# IoT_Pro_04.net
KiCad netlist of a schematic drawn in EAGLE
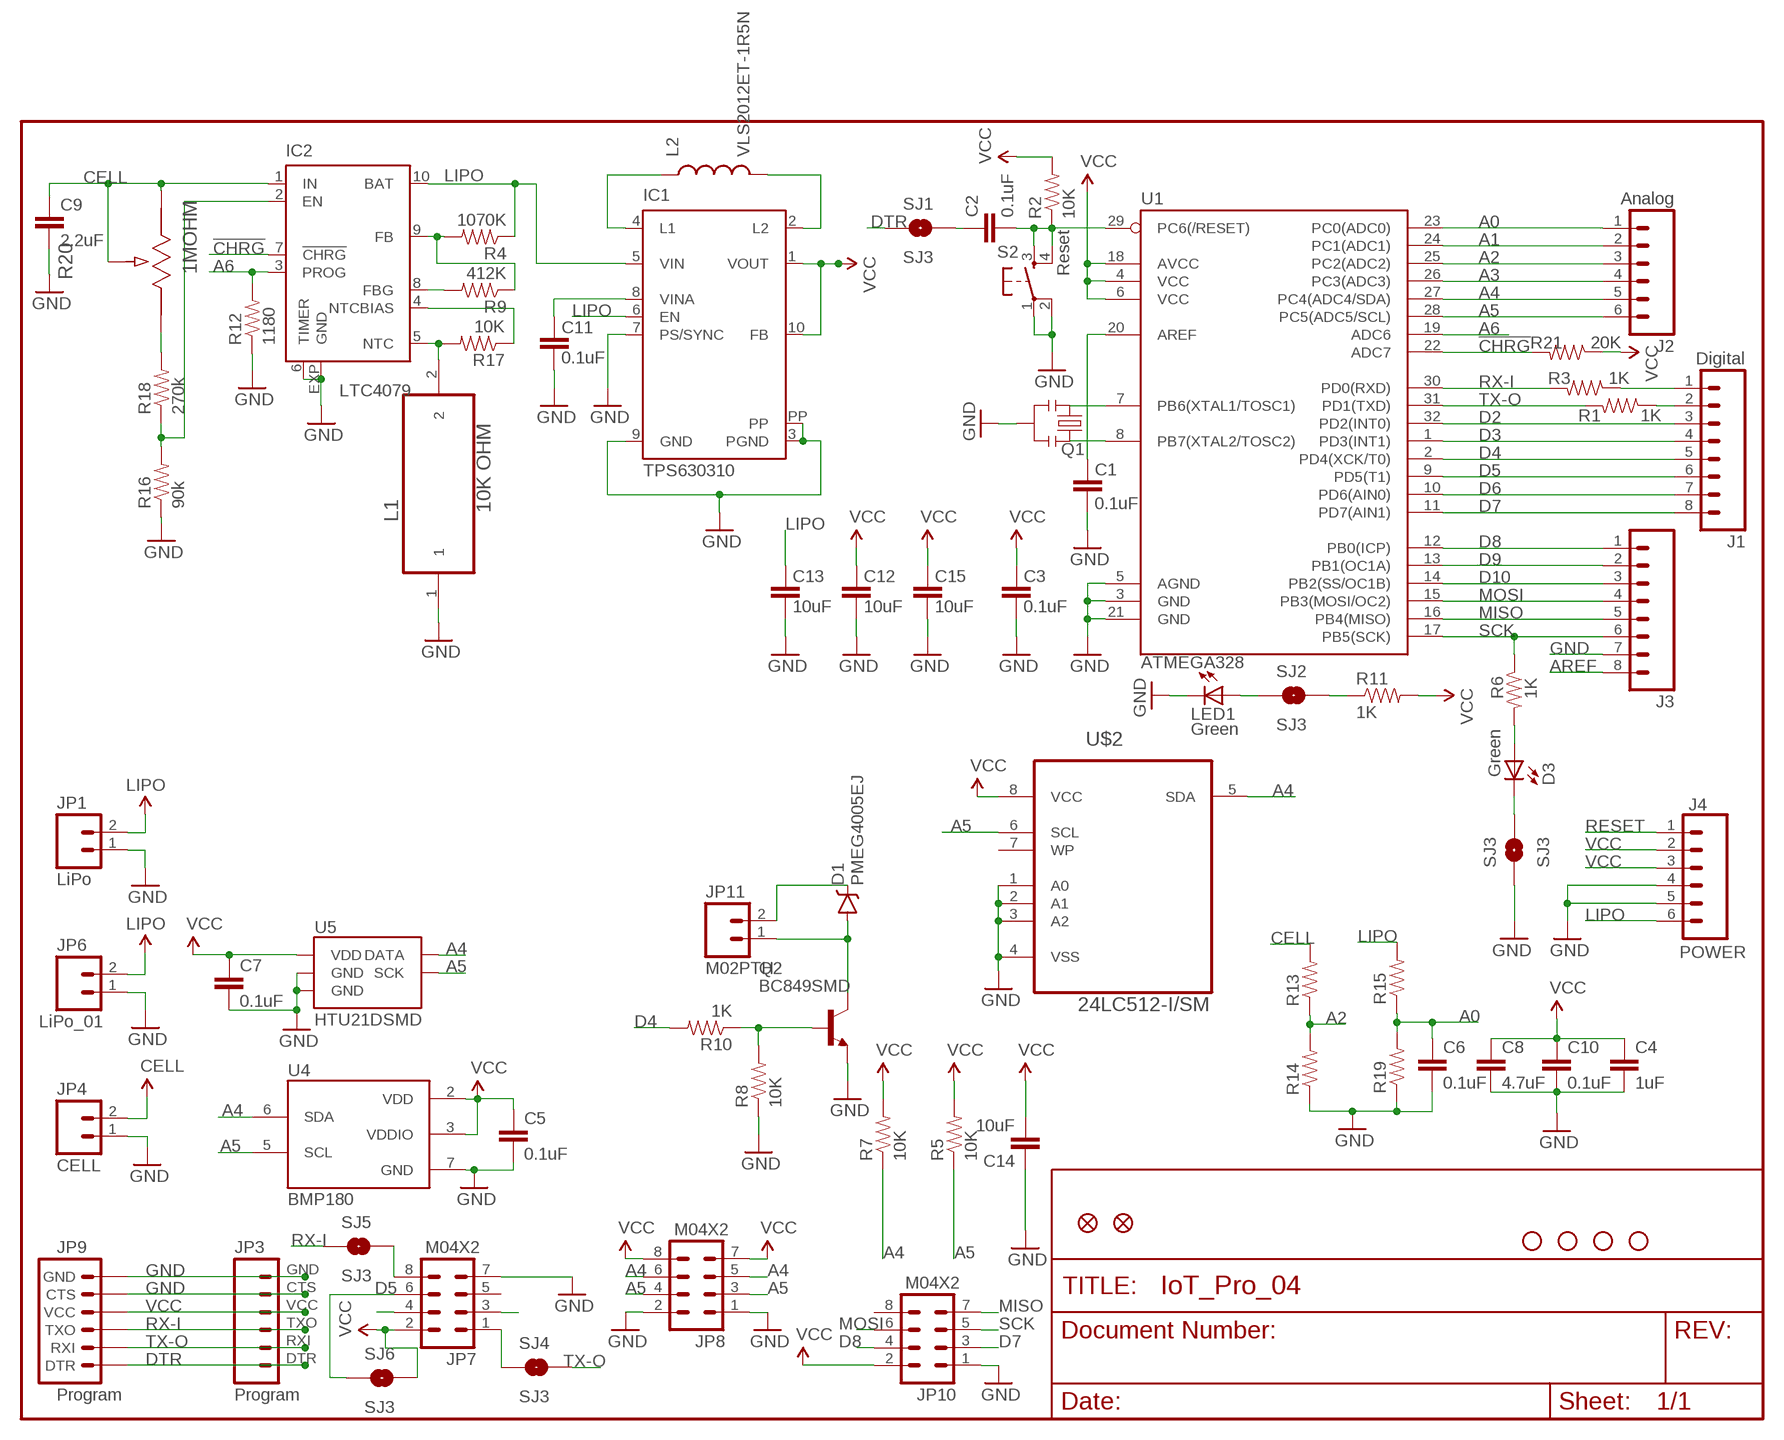
[diagram p0: schematic, sheet 1]

(export (version "E")
  (design (tool "Eeschema 10.0.6"))
  (components
    (comp (ref "C1")
      (value "0.1uF")
      (footprint "eagle-import:0805")
      (libsource (lib "eagle-import") (part "CAP0805"))
    )
    (comp (ref "C2")
      (value "0.1uF")
      (footprint "eagle-import:0805")
      (libsource (lib "eagle-import") (part "CAP0805"))
    )
    (comp (ref "C3")
      (value "0.1uF")
      (footprint "eagle-import:0805")
      (libsource (lib "eagle-import") (part "CAP0805"))
    )
    (comp (ref "C4")
      (value "1uF")
      (footprint "eagle-import:0805")
      (libsource (lib "eagle-import") (part "CAP0805"))
    )
    (comp (ref "C5")
      (value "0.1uF")
      (footprint "eagle-import:0805")
      (libsource (lib "eagle-import") (part "CAP0805"))
    )
    (comp (ref "C6")
      (value "0.1uF")
      (footprint "eagle-import:0805")
      (libsource (lib "eagle-import") (part "CAP0805"))
    )
    (comp (ref "C7")
      (value "0.1uF")
      (footprint "eagle-import:0805")
      (libsource (lib "eagle-import") (part "CAP0805"))
    )
    (comp (ref "C8")
      (value "4.7uF")
      (footprint "eagle-import:0805")
      (libsource (lib "eagle-import") (part "CAP0805"))
    )
    (comp (ref "C9")
      (value "2.2uF")
      (footprint "eagle-import:0805")
      (libsource (lib "eagle-import") (part "CAP0805"))
    )
    (comp (ref "C10")
      (value "0.1uF")
      (footprint "eagle-import:0805")
      (libsource (lib "eagle-import") (part "CAP0805"))
    )
    (comp (ref "C11")
      (value "0.1uF")
      (footprint "eagle-import:0805")
      (libsource (lib "eagle-import") (part "CAP0805"))
    )
    (comp (ref "C12")
      (value "10uF")
      (footprint "eagle-import:0805")
      (libsource (lib "eagle-import") (part "CAP0805"))
    )
    (comp (ref "C13")
      (value "10uF")
      (footprint "eagle-import:0805")
      (libsource (lib "eagle-import") (part "CAP0805"))
    )
    (comp (ref "C14")
      (value "10uF")
      (footprint "eagle-import:0805")
      (libsource (lib "eagle-import") (part "SparkFun-Passives_CAP0805"))
    )
    (comp (ref "C15")
      (value "10uF")
      (footprint "eagle-import:0805")
      (libsource (lib "eagle-import") (part "CAP0805"))
    )
    (comp (ref "D1")
      (value "PMEG4005EJ")
      (footprint "eagle-import:SOD-323")
      (libsource (lib "eagle-import") (part "DIODE-SCHOTTKY-PMEG4005EJ"))
    )
    (comp (ref "D3")
      (value "Green")
      (footprint "eagle-import:PLCC2")
      (libsource (lib "eagle-import") (part "_T679-?-1E1F1LG"))
    )
    (comp (ref "IC1")
      (value "TPS630310")
      (footprint "eagle-import:S-PDSO-N10")
      (fields (field (name "MPN") "TPS61200DRCT"))
      (libsource (lib "eagle-import") (part "TPS630310"))
    )
    (comp (ref "IC2")
      (value "LTC4079")
      (footprint "eagle-import:DFN10-3X3")
      (fields (field (name "MPN") "LTC4062EDD#PBF"))
      (libsource (lib "eagle-import") (part "LTC4079"))
    )
    (comp (ref "J1")
      (value "Digital")
      (footprint "eagle-import:1X08")
      (libsource (lib "eagle-import") (part "M081X08"))
    )
    (comp (ref "J2")
      (value "Analog")
      (footprint "eagle-import:1X06")
      (libsource (lib "eagle-import") (part "M06SIP"))
    )
    (comp (ref "J3")
      (value "M081X08")
      (footprint "eagle-import:1X08")
      (libsource (lib "eagle-import") (part "M081X08"))
    )
    (comp (ref "J4")
      (value "POWER")
      (footprint "eagle-import:1X06")
      (libsource (lib "eagle-import") (part "M06SIP"))
    )
    (comp (ref "JP1")
      (value "LiPo")
      (footprint "eagle-import:MOLEX-1X2")
      (libsource (lib "eagle-import") (part "SparkFun-Connectors_M02POLAR"))
    )
    (comp (ref "JP2")
      (value "FIDUCIAL1X2.5")
      (footprint "eagle-import:FIDUCIAL-1X2.5")
      (libsource (lib "eagle-import") (part "FIDUCIAL1X2.5"))
    )
    (comp (ref "JP3")
      (value "Program")
      (footprint "eagle-import:1X06")
      (libsource (lib "eagle-import") (part "SparkFun-Connectors_M06SIP"))
    )
    (comp (ref "JP4")
      (value "CELL")
      (footprint "eagle-import:MOLEX-1X2")
      (libsource (lib "eagle-import") (part "SparkFun-Connectors_M02POLAR"))
    )
    (comp (ref "JP5")
      (value "FIDUCIAL1X2.5")
      (footprint "eagle-import:FIDUCIAL-1X2.5")
      (libsource (lib "eagle-import") (part "FIDUCIAL1X2.5"))
    )
    (comp (ref "JP6")
      (value "LiPo_01")
      (footprint "eagle-import:1X02")
      (libsource (lib "eagle-import") (part "M02PTH"))
    )
    (comp (ref "JP7")
      (value "M04X2")
      (footprint "eagle-import:2X4")
      (libsource (lib "eagle-import") (part "M04X2"))
    )
    (comp (ref "JP8")
      (value "M04X2")
      (footprint "eagle-import:2X4")
      (libsource (lib "eagle-import") (part "M04X2"))
    )
    (comp (ref "JP9")
      (value "Program")
      (footprint "eagle-import:1X06-SMD")
      (libsource (lib "eagle-import") (part "ARDUINO_SERIAL_PROGRAMSMD"))
    )
    (comp (ref "JP10")
      (value "M04X2")
      (footprint "eagle-import:2X4")
      (libsource (lib "eagle-import") (part "M04X2"))
    )
    (comp (ref "JP11")
      (value "M02PTH")
      (footprint "eagle-import:1X02")
      (libsource (lib "eagle-import") (part "SparkFun-Connectors_M02PTH"))
    )
    (comp (ref "L1")
      (value "10K OHM")
      (footprint "eagle-import:THERM_B57421V2103J62")
      (fields (field (name "MPN") "B57421V2103J62") (field (name "TOLERANCE") "±5%"))
      (libsource (lib "eagle-import") (part "B57421V2103J62"))
    )
    (comp (ref "L2")
      (value "VLS2012ET-1R5N")
      (footprint "eagle-import:1007")
      (libsource (lib "eagle-import") (part "INDUCTOR1007"))
    )
    (comp (ref "LED1")
      (value "Green")
      (footprint "eagle-import:PLCC2")
      (libsource (lib "eagle-import") (part "_T679-?-1E1F1LG"))
    )
    (comp (ref "Q1")
      (value "8MHZ")
      (footprint "eagle-import:RESONATOR-SMD")
      (libsource (lib "eagle-import") (part "RESONATOR8MHZ"))
    )
    (comp (ref "Q2")
      (value "BC849SMD")
      (footprint "eagle-import:SOT23-BEC")
      (libsource (lib "eagle-import") (part "BC849SMD"))
    )
    (comp (ref "R1")
      (value "1K")
      (footprint "eagle-import:0805")
      (libsource (lib "eagle-import") (part "RESISTOR0805-RES"))
    )
    (comp (ref "R2")
      (value "10K")
      (footprint "eagle-import:0805")
      (libsource (lib "eagle-import") (part "RESISTOR0805-RES"))
    )
    (comp (ref "R3")
      (value "1K")
      (footprint "eagle-import:0805")
      (libsource (lib "eagle-import") (part "RESISTOR0805-RES"))
    )
    (comp (ref "R4")
      (value "1070K")
      (footprint "eagle-import:0805")
      (libsource (lib "eagle-import") (part "RESISTOR0805-RES"))
    )
    (comp (ref "R5")
      (value "10K")
      (footprint "eagle-import:0805")
      (libsource (lib "eagle-import") (part "RESISTOR0805-RES"))
    )
    (comp (ref "R6")
      (value "1K")
      (footprint "eagle-import:0805")
      (libsource (lib "eagle-import") (part "RESISTOR0805-RES"))
    )
    (comp (ref "R7")
      (value "10K")
      (footprint "eagle-import:0805")
      (libsource (lib "eagle-import") (part "RESISTOR0805-RES"))
    )
    (comp (ref "R8")
      (value "10K")
      (footprint "eagle-import:0805")
      (libsource (lib "eagle-import") (part "RESISTOR0805-RES"))
    )
    (comp (ref "R9")
      (value "412K")
      (footprint "eagle-import:0805")
      (libsource (lib "eagle-import") (part "RESISTOR0805-RES"))
    )
    (comp (ref "R10")
      (value "1K")
      (footprint "eagle-import:0805")
      (libsource (lib "eagle-import") (part "RESISTOR0805-RES"))
    )
    (comp (ref "R11")
      (value "1K")
      (footprint "eagle-import:0805")
      (libsource (lib "eagle-import") (part "RESISTOR0805-RES"))
    )
    (comp (ref "R12")
      (value "1180")
      (footprint "eagle-import:0805")
      (libsource (lib "eagle-import") (part "RESISTOR0805-RES"))
    )
    (comp (ref "R13")
      (value "RESISTOR0805-RES")
      (footprint "eagle-import:0805")
      (libsource (lib "eagle-import") (part "SparkFun-Passives_RESISTOR0805-RES"))
    )
    (comp (ref "R14")
      (value "RESISTOR0805-RES")
      (footprint "eagle-import:0805")
      (libsource (lib "eagle-import") (part "SparkFun-Passives_RESISTOR0805-RES"))
    )
    (comp (ref "R15")
      (value "RESISTOR0805-RES")
      (footprint "eagle-import:0805")
      (libsource (lib "eagle-import") (part "SparkFun-Passives_RESISTOR0805-RES"))
    )
    (comp (ref "R16")
      (value "90k")
      (footprint "eagle-import:0805")
      (libsource (lib "eagle-import") (part "RESISTOR0805-RES"))
    )
    (comp (ref "R17")
      (value "10K")
      (footprint "eagle-import:0805")
      (libsource (lib "eagle-import") (part "RESISTOR0805-RES"))
    )
    (comp (ref "R18")
      (value "270k")
      (footprint "eagle-import:0805")
      (libsource (lib "eagle-import") (part "RESISTOR0805-RES"))
    )
    (comp (ref "R19")
      (value "RESISTOR0805-RES")
      (footprint "eagle-import:0805")
      (libsource (lib "eagle-import") (part "SparkFun-Passives_RESISTOR0805-RES"))
    )
    (comp (ref "R20")
      (value "1MOHM")
      (footprint "eagle-import:POT_EVM2N")
      (fields (field (name "MPN") "EVM2NSX80B16") (field (name "TOLERANCE") "±25 %"))
      (libsource (lib "eagle-import") (part "EVM-2N2NSX80B16"))
    )
    (comp (ref "R21")
      (value "20K")
      (footprint "eagle-import:0805")
      (libsource (lib "eagle-import") (part "RESISTOR0805-RES"))
    )
    (comp (ref "S2")
      (value "Reset")
      (footprint "eagle-import:TACTILE_SWITCH_SMD")
      (libsource (lib "eagle-import") (part "TAC_SWITCHSMD"))
    )
    (comp (ref "SJ1")
      (value "SJ3")
      (footprint "eagle-import:SJ_2S-NOTRACE")
      (libsource (lib "eagle-import") (part "SOLDERJUMPERNC2"))
    )
    (comp (ref "SJ2")
      (value "SJ3")
      (footprint "eagle-import:SJ_2S-NOTRACE")
      (libsource (lib "eagle-import") (part "SOLDERJUMPERNC2"))
    )
    (comp (ref "SJ3")
      (value "SJ3")
      (footprint "eagle-import:SJ_2S-NOTRACE")
      (libsource (lib "eagle-import") (part "SOLDERJUMPERNC2"))
    )
    (comp (ref "SJ4")
      (value "SJ3")
      (footprint "eagle-import:SJ_2S-NOTRACE")
      (libsource (lib "eagle-import") (part "SOLDERJUMPERNC2"))
    )
    (comp (ref "SJ5")
      (value "SJ3")
      (footprint "eagle-import:SJ_2S-NOTRACE")
      (libsource (lib "eagle-import") (part "SOLDERJUMPERNC2"))
    )
    (comp (ref "SJ6")
      (value "SJ3")
      (footprint "eagle-import:SJ_2S-NOTRACE")
      (libsource (lib "eagle-import") (part "SOLDERJUMPERNC2"))
    )
    (comp (ref "U$1")
      (value "STAND-OFFTIGHT")
      (footprint "eagle-import:STAND-OFF-TIGHT")
      (libsource (lib "eagle-import") (part "STAND-OFFTIGHT"))
    )
    (comp (ref "U$2")
      (value "24LC512-I/SM")
      (footprint "eagle-import:SOIC127P794X203-8N")
      (libsource (lib "eagle-import") (part "24LC512-I/SM"))
    )
    (comp (ref "U$3")
      (value "STAND-OFFTIGHT")
      (footprint "eagle-import:STAND-OFF-TIGHT")
      (libsource (lib "eagle-import") (part "STAND-OFFTIGHT"))
    )
    (comp (ref "U$9")
      (value "STAND-OFFTIGHT")
      (footprint "eagle-import:STAND-OFF-TIGHT")
      (libsource (lib "eagle-import") (part "STAND-OFFTIGHT"))
    )
    (comp (ref "U$10")
      (value "STAND-OFFTIGHT")
      (footprint "eagle-import:STAND-OFF-TIGHT")
      (libsource (lib "eagle-import") (part "STAND-OFFTIGHT"))
    )
    (comp (ref "U1")
      (value "ATMEGA328")
      (footprint "eagle-import:TQFP32-08")
      (libsource (lib "eagle-import") (part "ATMEGA168"))
    )
    (comp (ref "U4")
      (value "BMP180")
      (footprint "eagle-import:BMP180")
      (libsource (lib "eagle-import") (part "BMP180"))
    )
    (comp (ref "U5")
      (value "HTU21DSMD")
      (footprint "eagle-import:HTU21D")
      (libsource (lib "eagle-import") (part "HTU21DSMD"))
    )
  )
  (nets
    (net (code "1") (name "/A0") (class "Default")
      (node (ref "C6") (pin "1") (pinfunction "1_1") (pintype "passive"))
      (node (ref "J2") (pin "1") (pinfunction "1_1") (pintype "passive"))
      (node (ref "R15") (pin "1") (pinfunction "1_1") (pintype "passive"))
      (node (ref "R19") (pin "2") (pinfunction "2_2") (pintype "passive"))
      (node (ref "U1") (pin "23") (pinfunction "PC0(ADC0)_23") (pintype "bidirectional"))
    )
    (net (code "2") (name "/A1") (class "Default")
      (node (ref "J2") (pin "2") (pinfunction "2_2") (pintype "passive"))
      (node (ref "U1") (pin "24") (pinfunction "PC1(ADC1)_24") (pintype "bidirectional"))
    )
    (net (code "3") (name "/A2") (class "Default")
      (node (ref "J2") (pin "3") (pinfunction "3_3") (pintype "passive"))
      (node (ref "R13") (pin "1") (pinfunction "1_1") (pintype "passive"))
      (node (ref "R14") (pin "2") (pinfunction "2_2") (pintype "passive"))
      (node (ref "U1") (pin "25") (pinfunction "PC2(ADC2)_25") (pintype "bidirectional"))
    )
    (net (code "4") (name "/A3") (class "Default")
      (node (ref "J2") (pin "4") (pinfunction "4_4") (pintype "passive"))
      (node (ref "U1") (pin "26") (pinfunction "PC3(ADC3)_26") (pintype "bidirectional"))
    )
    (net (code "5") (name "/A4") (class "Default")
      (node (ref "J2") (pin "5") (pinfunction "5_5") (pintype "passive"))
      (node (ref "JP8") (pin "5") (pinfunction "5_5") (pintype "passive"))
      (node (ref "JP8") (pin "6") (pinfunction "6_6") (pintype "passive"))
      (node (ref "R7") (pin "1") (pinfunction "1_1") (pintype "passive"))
      (node (ref "U$2") (pin "5") (pinfunction "SDA_5") (pintype "bidirectional"))
      (node (ref "U1") (pin "27") (pinfunction "PC4(ADC4/SDA)_27") (pintype "bidirectional"))
      (node (ref "U4") (pin "6") (pinfunction "SDA_6") (pintype "bidirectional"))
      (node (ref "U5") (pin "DATA") (pinfunction "DATA_DATA") (pintype "bidirectional"))
    )
    (net (code "6") (name "/A5") (class "Default")
      (node (ref "J2") (pin "6") (pinfunction "6_6") (pintype "passive"))
      (node (ref "JP8") (pin "3") (pinfunction "3_3") (pintype "passive"))
      (node (ref "JP8") (pin "4") (pinfunction "4_4") (pintype "passive"))
      (node (ref "R5") (pin "1") (pinfunction "1_1") (pintype "passive"))
      (node (ref "U$2") (pin "6") (pinfunction "SCL_6") (pintype "input"))
      (node (ref "U1") (pin "28") (pinfunction "PC5(ADC5/SCL)_28") (pintype "bidirectional"))
      (node (ref "U4") (pin "5") (pinfunction "SCL_5") (pintype "input"))
      (node (ref "U5") (pin "SCK") (pinfunction "SCK_SCK") (pintype "input"))
    )
    (net (code "7") (name "/A6") (class "Default")
      (node (ref "IC2") (pin "3") (pinfunction "PROG_3") (pintype "passive"))
      (node (ref "R12") (pin "2") (pinfunction "2_2") (pintype "passive"))
      (node (ref "U1") (pin "19") (pinfunction "ADC6_19") (pintype "bidirectional"))
    )
    (net (code "8") (name "/AREF") (class "Default")
      (node (ref "C1") (pin "2") (pinfunction "2_2") (pintype "passive"))
      (node (ref "J3") (pin "8") (pinfunction "8_8") (pintype "passive"))
      (node (ref "U1") (pin "20") (pinfunction "AREF_20") (pintype "bidirectional"))
    )
    (net (code "9") (name "/D2") (class "Default")
      (node (ref "J1") (pin "3") (pinfunction "3_3") (pintype "passive"))
      (node (ref "U1") (pin "32") (pinfunction "PD2(INT0)_32") (pintype "bidirectional"))
    )
    (net (code "10") (name "/D3") (class "Default")
      (node (ref "J1") (pin "4") (pinfunction "4_4") (pintype "passive"))
      (node (ref "U1") (pin "1") (pinfunction "PD3(INT1)_1") (pintype "bidirectional"))
    )
    (net (code "11") (name "/D4") (class "Default")
      (node (ref "J1") (pin "5") (pinfunction "5_5") (pintype "passive"))
      (node (ref "R10") (pin "2") (pinfunction "2_2") (pintype "passive"))
      (node (ref "U1") (pin "2") (pinfunction "PD4(XCK/T0)_2") (pintype "bidirectional"))
    )
    (net (code "12") (name "/D5") (class "Default")
      (node (ref "J1") (pin "6") (pinfunction "6_6") (pintype "passive"))
      (node (ref "JP7") (pin "6") (pinfunction "6_6") (pintype "passive"))
      (node (ref "SJ6") (pin "1") (pinfunction "1_1") (pintype "passive"))
      (node (ref "U1") (pin "9") (pinfunction "PD5(T1)_9") (pintype "bidirectional"))
    )
    (net (code "13") (name "/D6") (class "Default")
      (node (ref "J1") (pin "7") (pinfunction "7_7") (pintype "passive"))
      (node (ref "U1") (pin "10") (pinfunction "PD6(AIN0)_10") (pintype "bidirectional"))
    )
    (net (code "14") (name "/D7") (class "Default")
      (node (ref "J1") (pin "8") (pinfunction "8_8") (pintype "passive"))
      (node (ref "JP10") (pin "3") (pinfunction "3_3") (pintype "passive"))
      (node (ref "U1") (pin "11") (pinfunction "PD7(AIN1)_11") (pintype "bidirectional"))
    )
    (net (code "15") (name "/D8") (class "Default")
      (node (ref "J3") (pin "1") (pinfunction "1_1") (pintype "passive"))
      (node (ref "JP10") (pin "4") (pinfunction "4_4") (pintype "passive"))
      (node (ref "U1") (pin "12") (pinfunction "PB0(ICP)_12") (pintype "bidirectional"))
    )
    (net (code "16") (name "/D9") (class "Default")
      (node (ref "J3") (pin "2") (pinfunction "2_2") (pintype "passive"))
      (node (ref "U1") (pin "13") (pinfunction "PB1(OC1A)_13") (pintype "bidirectional"))
    )
    (net (code "17") (name "/D10") (class "Default")
      (node (ref "J3") (pin "3") (pinfunction "3_3") (pintype "passive"))
      (node (ref "U1") (pin "14") (pinfunction "PB2(SS/OC1B)_14") (pintype "bidirectional"))
    )
    (net (code "18") (name "/DTR") (class "Default")
      (node (ref "JP3") (pin "DTR") (pinfunction "1_DTR") (pintype "passive"))
      (node (ref "JP9") (pin "1") (pinfunction "DTR_1") (pintype "passive"))
      (node (ref "SJ1") (pin "1") (pinfunction "1_1") (pintype "passive"))
    )
    (net (code "19") (name "/MISO") (class "Default")
      (node (ref "J3") (pin "5") (pinfunction "5_5") (pintype "passive"))
      (node (ref "JP10") (pin "7") (pinfunction "7_7") (pintype "passive"))
      (node (ref "U1") (pin "16") (pinfunction "PB4(MISO)_16") (pintype "bidirectional"))
    )
    (net (code "20") (name "/MOSI") (class "Default")
      (node (ref "J3") (pin "4") (pinfunction "4_4") (pintype "passive"))
      (node (ref "JP10") (pin "6") (pinfunction "6_6") (pintype "passive"))
      (node (ref "U1") (pin "15") (pinfunction "PB3(MOSI/OC2)_15") (pintype "bidirectional"))
    )
    (net (code "21") (name "/RESET") (class "Default")
      (node (ref "C2") (pin "2") (pinfunction "2_2") (pintype "passive"))
      (node (ref "J4") (pin "1") (pinfunction "1_1") (pintype "passive"))
      (node (ref "R2") (pin "1") (pinfunction "1_1") (pintype "passive"))
      (node (ref "S2") (pin "3") (pinfunction "3_3") (pintype "passive"))
      (node (ref "S2") (pin "4") (pinfunction "4_4") (pintype "passive"))
      (node (ref "U1") (pin "29") (pinfunction "PC6(/RESET)_29") (pintype "bidirectional"))
    )
    (net (code "22") (name "/RX-I") (class "Default")
      (node (ref "JP3") (pin "TXO") (pinfunction "3_TXO") (pintype "passive"))
      (node (ref "JP9") (pin "3") (pinfunction "TXO_3") (pintype "passive"))
      (node (ref "R3") (pin "2") (pinfunction "2_2") (pintype "passive"))
      (node (ref "SJ5") (pin "1") (pinfunction "1_1") (pintype "passive"))
      (node (ref "U1") (pin "30") (pinfunction "PD0(RXD)_30") (pintype "bidirectional"))
    )
    (net (code "23") (name "/SCK") (class "Default")
      (node (ref "J3") (pin "6") (pinfunction "6_6") (pintype "passive"))
      (node (ref "JP10") (pin "5") (pinfunction "5_5") (pintype "passive"))
      (node (ref "R6") (pin "1") (pinfunction "1_1") (pintype "passive"))
      (node (ref "U1") (pin "17") (pinfunction "PB5(SCK)_17") (pintype "bidirectional"))
    )
    (net (code "24") (name "/TX-O") (class "Default")
      (node (ref "JP3") (pin "RXI") (pinfunction "2_RXI") (pintype "passive"))
      (node (ref "JP9") (pin "2") (pinfunction "RXI_2") (pintype "passive"))
      (node (ref "R1") (pin "2") (pinfunction "2_2") (pintype "passive"))
      (node (ref "SJ4") (pin "2") (pinfunction "2_2") (pintype "passive"))
      (node (ref "U1") (pin "31") (pinfunction "PD1(TXD)_31") (pintype "bidirectional"))
    )
    (net (code "25") (name "/~{CHRG}") (class "Default")
      (node (ref "IC2") (pin "7") (pinfunction "~{CHRG}_7") (pintype "input"))
      (node (ref "R21") (pin "2") (pinfunction "2_2") (pintype "passive"))
      (node (ref "U1") (pin "22") (pinfunction "ADC7_22") (pintype "bidirectional"))
    )
    (net (code "26") (name "CELL") (class "Default")
      (node (ref "C9") (pin "1") (pinfunction "1_1") (pintype "passive"))
      (node (ref "IC2") (pin "1") (pinfunction "IN_1") (pintype "passive"))
      (node (ref "JP4") (pin "2") (pinfunction "2_2") (pintype "passive"))
      (node (ref "R13") (pin "2") (pinfunction "2_2") (pintype "passive"))
      (node (ref "R20") (pin "2") (pinfunction "2_2") (pintype "passive"))
      (node (ref "R20") (pin "3") (pinfunction "3_3") (pintype "passive"))
    )
    (net (code "27") (name "GND") (class "Default")
      (node (ref "C1") (pin "1") (pinfunction "1_1") (pintype "passive"))
      (node (ref "C10") (pin "2") (pinfunction "2_2") (pintype "passive"))
      (node (ref "C11") (pin "1") (pinfunction "1_1") (pintype "passive"))
      (node (ref "C12") (pin "1") (pinfunction "1_1") (pintype "passive"))
      (node (ref "C13") (pin "1") (pinfunction "1_1") (pintype "passive"))
      (node (ref "C14") (pin "1") (pinfunction "1_1") (pintype "passive"))
      (node (ref "C15") (pin "1") (pinfunction "1_1") (pintype "passive"))
      (node (ref "C3") (pin "1") (pinfunction "1_1") (pintype "passive"))
      (node (ref "C4") (pin "2") (pinfunction "2_2") (pintype "passive"))
      (node (ref "C5") (pin "2") (pinfunction "2_2") (pintype "passive"))
      (node (ref "C6") (pin "2") (pinfunction "2_2") (pintype "passive"))
      (node (ref "C7") (pin "2") (pinfunction "2_2") (pintype "passive"))
      (node (ref "C8") (pin "2") (pinfunction "2_2") (pintype "passive"))
      (node (ref "C9") (pin "2") (pinfunction "2_2") (pintype "passive"))
      (node (ref "IC1") (pin "3") (pinfunction "PGND_3") (pintype "power_in"))
      (node (ref "IC1") (pin "7") (pinfunction "PS/SYNC_7") (pintype "input"))
      (node (ref "IC1") (pin "9") (pinfunction "GND_9") (pintype "power_in"))
      (node (ref "IC1") (pin "PP") (pinfunction "PP_PP") (pintype "power_in"))
      (node (ref "IC2") (pin "6") (pinfunction "TIMER_6") (pintype "input"))
      (node (ref "IC2") (pin "EXP") (pinfunction "GND_EXP") (pintype "power_in"))
      (node (ref "J3") (pin "7") (pinfunction "7_7") (pintype "passive"))
      (node (ref "J4") (pin "4") (pinfunction "4_4") (pintype "passive"))
      (node (ref "J4") (pin "5") (pinfunction "5_5") (pintype "passive"))
      (node (ref "JP1") (pin "1") (pinfunction "1_1") (pintype "passive"))
      (node (ref "JP10") (pin "1") (pinfunction "1_1") (pintype "passive"))
      (node (ref "JP3") (pin "CTS") (pinfunction "5_CTS") (pintype "passive"))
      (node (ref "JP3") (pin "GND") (pinfunction "6_GND") (pintype "passive"))
      (node (ref "JP4") (pin "1") (pinfunction "1_1") (pintype "passive"))
      (node (ref "JP6") (pin "1") (pinfunction "1_1") (pintype "passive"))
      (node (ref "JP7") (pin "7") (pinfunction "7_7") (pintype "passive"))
      (node (ref "JP8") (pin "1") (pinfunction "1_1") (pintype "passive"))
      (node (ref "JP8") (pin "2") (pinfunction "2_2") (pintype "passive"))
      (node (ref "JP9") (pin "5") (pinfunction "CTS_5") (pintype "passive"))
      (node (ref "JP9") (pin "6") (pinfunction "GND_6") (pintype "passive"))
      (node (ref "L1") (pin "1") (pinfunction "1_1") (pintype "passive"))
      (node (ref "LED1") (pin "C") (pinfunction "C_C") (pintype "passive"))
      (node (ref "Q1") (pin "2") (pinfunction "2_2") (pintype "passive"))
      (node (ref "Q2") (pin "E") (pinfunction "E_E") (pintype "passive"))
      (node (ref "R12") (pin "1") (pinfunction "1_1") (pintype "passive"))
      (node (ref "R14") (pin "1") (pinfunction "1_1") (pintype "passive"))
      (node (ref "R16") (pin "1") (pinfunction "1_1") (pintype "passive"))
      (node (ref "R19") (pin "1") (pinfunction "1_1") (pintype "passive"))
      (node (ref "R8") (pin "1") (pinfunction "1_1") (pintype "passive"))
      (node (ref "S2") (pin "1") (pinfunction "1_1") (pintype "passive"))
      (node (ref "S2") (pin "2") (pinfunction "2_2") (pintype "passive"))
      (node (ref "SJ3") (pin "1") (pinfunction "1_1") (pintype "passive"))
      (node (ref "U$2") (pin "1") (pinfunction "A0_1") (pintype "input"))
      (node (ref "U$2") (pin "2") (pinfunction "A1_2") (pintype "input"))
      (node (ref "U$2") (pin "3") (pinfunction "A2_3") (pintype "input"))
      (node (ref "U$2") (pin "4") (pinfunction "VSS_4") (pintype "passive"))
      (node (ref "U1") (pin "21") (pinfunction "GND_21") (pintype "bidirectional"))
      (node (ref "U1") (pin "3") (pinfunction "GND_3") (pintype "bidirectional"))
      (node (ref "U1") (pin "5") (pinfunction "AGND_5") (pintype "bidirectional"))
      (node (ref "U4") (pin "7") (pinfunction "GND_7") (pintype "power_in"))
      (node (ref "U5") (pin "7") (pinfunction "GND_7") (pintype "power_in"))
      (node (ref "U5") (pin "GND") (pinfunction "GND_GND") (pintype "power_in"))
    )
    (net (code "28") (name "LIPO") (class "Default")
      (node (ref "C13") (pin "2") (pinfunction "2_2") (pintype "passive"))
      (node (ref "IC1") (pin "5") (pinfunction "VIN_5") (pintype "input"))
      (node (ref "IC1") (pin "6") (pinfunction "EN_6") (pintype "input"))
      (node (ref "IC2") (pin "10") (pinfunction "BAT_10") (pintype "power_in"))
      (node (ref "J4") (pin "6") (pinfunction "6_6") (pintype "passive"))
      (node (ref "JP1") (pin "2") (pinfunction "2_2") (pintype "passive"))
      (node (ref "JP6") (pin "2") (pinfunction "2_2") (pintype "passive"))
      (node (ref "R15") (pin "2") (pinfunction "2_2") (pintype "passive"))
      (node (ref "R4") (pin "1") (pinfunction "1_1") (pintype "passive"))
    )
    (net (code "29") (name "Net-(C2-Pad1)") (class "Default")
      (node (ref "C2") (pin "1") (pinfunction "1_1") (pintype "passive"))
      (node (ref "SJ1") (pin "2") (pinfunction "2_2") (pintype "passive"))
    )
    (net (code "30") (name "Net-(D1-PadA)") (class "Default")
      (node (ref "D1") (pin "A") (pinfunction "A_A") (pintype "passive"))
      (node (ref "JP11") (pin "1") (pinfunction "1_1") (pintype "passive"))
      (node (ref "Q2") (pin "C") (pinfunction "C_C") (pintype "passive"))
    )
    (net (code "31") (name "Net-(D1-PadC)") (class "Default")
      (node (ref "D1") (pin "C") (pinfunction "C_C") (pintype "passive"))
      (node (ref "JP11") (pin "2") (pinfunction "2_2") (pintype "passive"))
    )
    (net (code "32") (name "Net-(D3-PadA)") (class "Default")
      (node (ref "D3") (pin "A") (pinfunction "A_A") (pintype "passive"))
      (node (ref "R6") (pin "2") (pinfunction "2_2") (pintype "passive"))
    )
    (net (code "33") (name "Net-(D3-PadC)") (class "Default")
      (node (ref "D3") (pin "C") (pinfunction "C_C") (pintype "passive"))
      (node (ref "SJ3") (pin "2") (pinfunction "2_2") (pintype "passive"))
    )
    (net (code "34") (name "Net-(IC1-L1)") (class "Default")
      (node (ref "IC1") (pin "4") (pinfunction "L1_4") (pintype "input"))
      (node (ref "L2") (pin "1") (pinfunction "1_1") (pintype "passive"))
    )
    (net (code "35") (name "Net-(IC1-L2)") (class "Default")
      (node (ref "IC1") (pin "2") (pinfunction "L2_2") (pintype "bidirectional"))
      (node (ref "L2") (pin "2") (pinfunction "2_2") (pintype "passive"))
    )
    (net (code "36") (name "Net-(IC1-VINA)") (class "Default")
      (node (ref "C11") (pin "2") (pinfunction "2_2") (pintype "passive"))
      (node (ref "IC1") (pin "8") (pinfunction "VINA_8") (pintype "input"))
    )
    (net (code "37") (name "Net-(IC2-EN)") (class "Default")
      (node (ref "IC2") (pin "2") (pinfunction "EN_2") (pintype "input"))
      (node (ref "R16") (pin "2") (pinfunction "2_2") (pintype "passive"))
      (node (ref "R18") (pin "1") (pinfunction "1_1") (pintype "passive"))
    )
    (net (code "38") (name "Net-(IC2-FB)") (class "Default")
      (node (ref "IC2") (pin "9") (pinfunction "FB_9") (pintype "passive"))
      (node (ref "R4") (pin "2") (pinfunction "2_2") (pintype "passive"))
      (node (ref "R9") (pin "1") (pinfunction "1_1") (pintype "passive"))
    )
    (net (code "39") (name "Net-(IC2-FBG)") (class "Default")
      (node (ref "IC2") (pin "8") (pinfunction "FBG_8") (pintype "passive"))
      (node (ref "R9") (pin "2") (pinfunction "2_2") (pintype "passive"))
    )
    (net (code "40") (name "Net-(IC2-NTC)") (class "Default")
      (node (ref "IC2") (pin "5") (pinfunction "NTC_5") (pintype "open_collector"))
      (node (ref "L1") (pin "2") (pinfunction "2_2") (pintype "passive"))
      (node (ref "R17") (pin "2") (pinfunction "2_2") (pintype "passive"))
    )
    (net (code "41") (name "Net-(IC2-NTCBIAS)") (class "Default")
      (node (ref "IC2") (pin "4") (pinfunction "NTCBIAS_4") (pintype "open_collector"))
      (node (ref "R17") (pin "1") (pinfunction "1_1") (pintype "passive"))
    )
    (net (code "42") (name "Net-(J1-Pad1)") (class "Default")
      (node (ref "J1") (pin "1") (pinfunction "1_1") (pintype "passive"))
      (node (ref "R3") (pin "1") (pinfunction "1_1") (pintype "passive"))
    )
    (net (code "43") (name "Net-(J1-Pad2)") (class "Default")
      (node (ref "J1") (pin "2") (pinfunction "2_2") (pintype "passive"))
      (node (ref "R1") (pin "1") (pinfunction "1_1") (pintype "passive"))
    )
    (net (code "44") (name "Net-(JP7-Pad1)") (class "Default")
      (node (ref "JP7") (pin "1") (pinfunction "1_1") (pintype "passive"))
      (node (ref "SJ4") (pin "1") (pinfunction "1_1") (pintype "passive"))
    )
    (net (code "45") (name "Net-(JP7-Pad8)") (class "Default")
      (node (ref "JP7") (pin "8") (pinfunction "8_8") (pintype "passive"))
      (node (ref "SJ5") (pin "2") (pinfunction "2_2") (pintype "passive"))
    )
    (net (code "46") (name "Net-(LED1-PadA)") (class "Default")
      (node (ref "LED1") (pin "A") (pinfunction "A_A") (pintype "passive"))
      (node (ref "SJ2") (pin "1") (pinfunction "1_1") (pintype "passive"))
    )
    (net (code "47") (name "Net-(Q2-PadB)") (class "Default")
      (node (ref "Q2") (pin "B") (pinfunction "B_B") (pintype "passive"))
      (node (ref "R10") (pin "1") (pinfunction "1_1") (pintype "passive"))
      (node (ref "R8") (pin "2") (pinfunction "2_2") (pintype "passive"))
    )
    (net (code "48") (name "Net-(R11-Pad1)") (class "Default")
      (node (ref "R11") (pin "1") (pinfunction "1_1") (pintype "passive"))
      (node (ref "SJ2") (pin "2") (pinfunction "2_2") (pintype "passive"))
    )
    (net (code "49") (name "Net-(R18-Pad2)") (class "Default")
      (node (ref "R18") (pin "2") (pinfunction "2_2") (pintype "passive"))
      (node (ref "R20") (pin "1") (pinfunction "1_1") (pintype "passive"))
    )
    (net (code "50") (name "Net-(U1-PB6(XTAL1{slash}TOSC1))") (class "Default")
      (node (ref "Q1") (pin "3") (pinfunction "3_3") (pintype "passive"))
      (node (ref "U1") (pin "7") (pinfunction "PB6(XTAL1/TOSC1)_7") (pintype "bidirectional"))
    )
    (net (code "51") (name "Net-(U1-PB7(XTAL2{slash}TOSC2))") (class "Default")
      (node (ref "Q1") (pin "1") (pinfunction "1_1") (pintype "passive"))
      (node (ref "U1") (pin "8") (pinfunction "PB7(XTAL2/TOSC2)_8") (pintype "bidirectional"))
    )
    (net (code "52") (name "VCC") (class "Default")
      (node (ref "C10") (pin "1") (pinfunction "1_1") (pintype "passive"))
      (node (ref "C12") (pin "2") (pinfunction "2_2") (pintype "passive"))
      (node (ref "C14") (pin "2") (pinfunction "2_2") (pintype "passive"))
      (node (ref "C15") (pin "2") (pinfunction "2_2") (pintype "passive"))
      (node (ref "C3") (pin "2") (pinfunction "2_2") (pintype "passive"))
      (node (ref "C4") (pin "1") (pinfunction "1_1") (pintype "passive"))
      (node (ref "C5") (pin "1") (pinfunction "1_1") (pintype "passive"))
      (node (ref "C7") (pin "1") (pinfunction "1_1") (pintype "passive"))
      (node (ref "C8") (pin "1") (pinfunction "1_1") (pintype "passive"))
      (node (ref "IC1") (pin "1") (pinfunction "VOUT_1") (pintype "passive"))
      (node (ref "IC1") (pin "10") (pinfunction "FB_10") (pintype "input"))
      (node (ref "J4") (pin "2") (pinfunction "2_2") (pintype "passive"))
      (node (ref "J4") (pin "3") (pinfunction "3_3") (pintype "passive"))
      (node (ref "JP10") (pin "2") (pinfunction "2_2") (pintype "passive"))
      (node (ref "JP3") (pin "VCC") (pinfunction "4_VCC") (pintype "passive"))
      (node (ref "JP7") (pin "2") (pinfunction "2_2") (pintype "passive"))
      (node (ref "JP8") (pin "7") (pinfunction "7_7") (pintype "passive"))
      (node (ref "JP8") (pin "8") (pinfunction "8_8") (pintype "passive"))
      (node (ref "JP9") (pin "4") (pinfunction "VCC_4") (pintype "passive"))
      (node (ref "R11") (pin "2") (pinfunction "2_2") (pintype "passive"))
      (node (ref "R2") (pin "2") (pinfunction "2_2") (pintype "passive"))
      (node (ref "R21") (pin "1") (pinfunction "1_1") (pintype "passive"))
      (node (ref "R5") (pin "2") (pinfunction "2_2") (pintype "passive"))
      (node (ref "R7") (pin "2") (pinfunction "2_2") (pintype "passive"))
      (node (ref "SJ6") (pin "2") (pinfunction "2_2") (pintype "passive"))
      (node (ref "U$2") (pin "8") (pinfunction "VCC_8") (pintype "power_in"))
      (node (ref "U1") (pin "18") (pinfunction "AVCC_18") (pintype "bidirectional"))
      (node (ref "U1") (pin "4") (pinfunction "VCC_4") (pintype "bidirectional"))
      (node (ref "U1") (pin "6") (pinfunction "VCC_6") (pintype "bidirectional"))
      (node (ref "U4") (pin "2") (pinfunction "VDD_2") (pintype "power_in"))
      (node (ref "U4") (pin "3") (pinfunction "VDDIO_3") (pintype "power_in"))
      (node (ref "U5") (pin "VDD") (pinfunction "VDD_VDD") (pintype "power_in"))
    )
    (net (code "53") (name "unconnected-(JP7-Pad3)") (class "Default")
      (node (ref "JP7") (pin "3") (pinfunction "3_3") (pintype "passive"))
    )
    (net (code "54") (name "unconnected-(JP7-Pad4)") (class "Default")
      (node (ref "JP7") (pin "4") (pinfunction "4_4") (pintype "passive"))
    )
    (net (code "55") (name "unconnected-(JP7-Pad5)") (class "Default")
      (node (ref "JP7") (pin "5") (pinfunction "5_5") (pintype "passive"))
    )
    (net (code "56") (name "unconnected-(JP10-Pad8)") (class "Default")
      (node (ref "JP10") (pin "8") (pinfunction "8_8") (pintype "passive"))
    )
    (net (code "57") (name "unconnected-(U$2-WP-Pad7)") (class "Default")
      (node (ref "U$2") (pin "7") (pinfunction "WP_7") (pintype "input"))
    )
  )
)
